# Qwiic_Atmospheric_Sensor.net
KiCad netlist of a schematic drawn in EAGLE
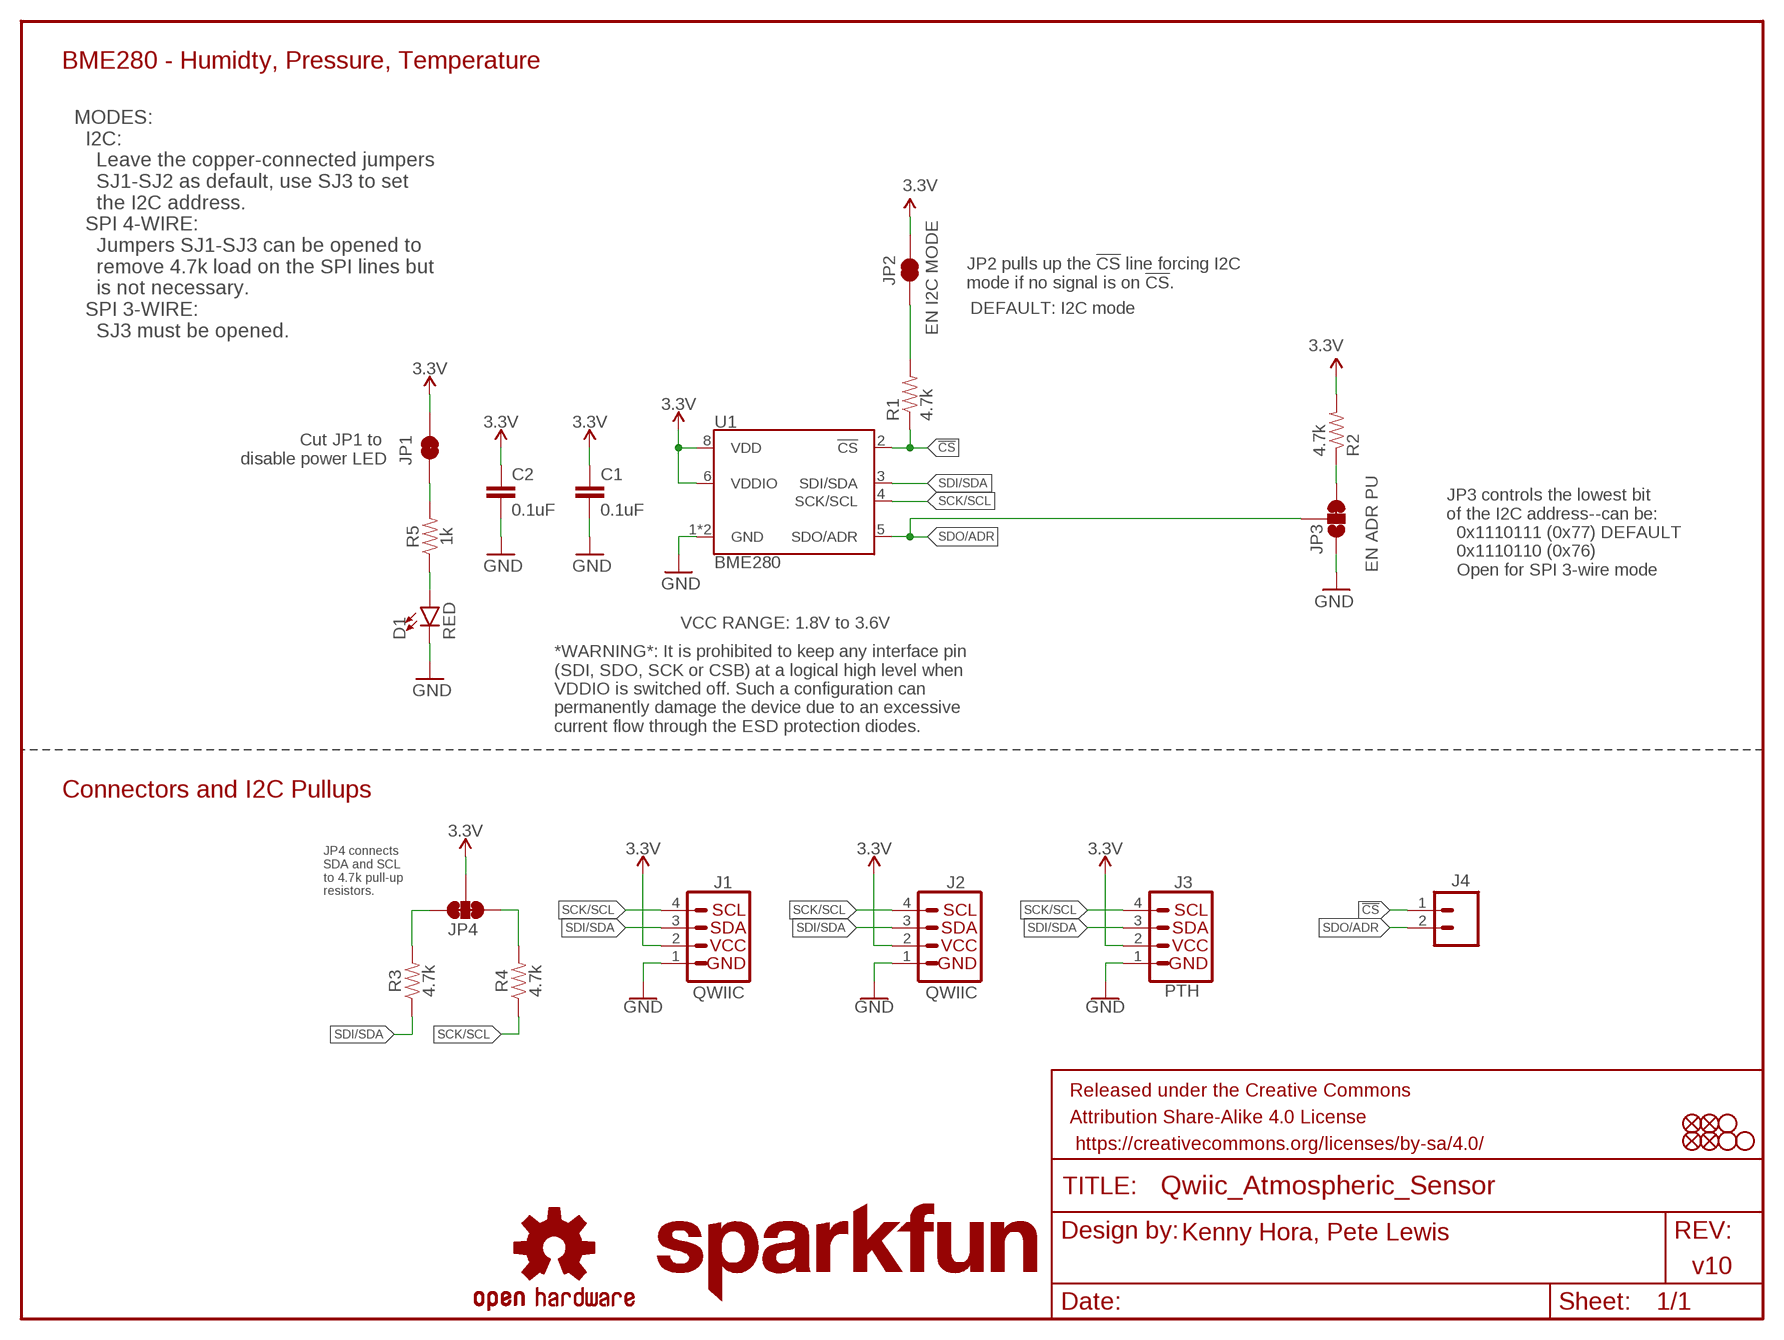
[diagram p0: schematic, sheet 1]

(export (version "E")
  (design (tool "Eeschema 10.0.6"))
  (components
    (comp (ref "C1")
      (value "0.1uF")
      (footprint "eagle-import:0603")
      (libsource (lib "eagle-import") (part "0.1UF-0603-25V-(+80/-20%)"))
    )
    (comp (ref "C2")
      (value "0.1uF")
      (footprint "eagle-import:0603")
      (libsource (lib "eagle-import") (part "0.1UF-0603-25V-(+80/-20%)"))
    )
    (comp (ref "D1")
      (value "RED")
      (footprint "eagle-import:LED-0603")
      (libsource (lib "eagle-import") (part "LED-RED0603"))
    )
    (comp (ref "FD1")
      (value "FIDUCIAL1X2")
      (footprint "eagle-import:FIDUCIAL-1X2")
      (libsource (lib "eagle-import") (part "FIDUCIAL1X2"))
    )
    (comp (ref "FD2")
      (value "FIDUCIAL1X2")
      (footprint "eagle-import:FIDUCIAL-1X2")
      (libsource (lib "eagle-import") (part "FIDUCIAL1X2"))
    )
    (comp (ref "FD3")
      (value "FIDUCIAL1X2")
      (footprint "eagle-import:FIDUCIAL-1X2")
      (libsource (lib "eagle-import") (part "FIDUCIAL1X2"))
    )
    (comp (ref "FD4")
      (value "FIDUCIAL1X2")
      (footprint "eagle-import:FIDUCIAL-1X2")
      (libsource (lib "eagle-import") (part "FIDUCIAL1X2"))
    )
    (comp (ref "FRAME1")
      (value "FRAME-LETTER")
      (footprint "eagle-import:CREATIVE_COMMONS")
      (libsource (lib "eagle-import") (part "FRAME-LETTER"))
    )
    (comp (ref "H1")
      (value "STAND-OFF")
      (footprint "eagle-import:STAND-OFF")
      (libsource (lib "eagle-import") (part "STAND-OFF"))
    )
    (comp (ref "H2")
      (value "STAND-OFF")
      (footprint "eagle-import:STAND-OFF")
      (libsource (lib "eagle-import") (part "STAND-OFF"))
    )
    (comp (ref "H4")
      (value "STAND-OFF")
      (footprint "eagle-import:STAND-OFF")
      (libsource (lib "eagle-import") (part "STAND-OFF"))
    )
    (comp (ref "J1")
      (value "QWIIC")
      (footprint "eagle-import:JST04_1MM_RA")
      (libsource (lib "eagle-import") (part "I2C_STANDARDQWIIC"))
    )
    (comp (ref "J2")
      (value "QWIIC")
      (footprint "eagle-import:JST04_1MM_RA")
      (libsource (lib "eagle-import") (part "I2C_STANDARDQWIIC"))
    )
    (comp (ref "J3")
      (value "PTH")
      (footprint "eagle-import:1X04_NO_SILK")
      (libsource (lib "eagle-import") (part "I2C_STANDARD_NO_SILK"))
    )
    (comp (ref "J4")
      (value "CONN_021X02_NO_SILK")
      (footprint "eagle-import:1X02_NO_SILK")
      (libsource (lib "eagle-import") (part "CONN_021X02_NO_SILK"))
    )
    (comp (ref "JP1")
      (value "JUMPER-SMT_2_NC_TRACE_NO-SILK")
      (footprint "eagle-import:SMT-JUMPER_2_NC_TRACE_NO-SILK")
      (libsource (lib "eagle-import") (part "JUMPER-SMT_2_NC_TRACE_NO-SILK"))
    )
    (comp (ref "JP2")
      (value "EN I2C MODE")
      (footprint "eagle-import:PAD-JUMPER-2-NC_BY_TRACE_NO_SILK")
      (libsource (lib "eagle-import") (part "JUMPER-PAD-2-NC_BY_TRACENO_SILK"))
    )
    (comp (ref "JP3")
      (value "EN ADR PU")
      (footprint "eagle-import:SMT-JUMPER_3_1-NC_TRACE_NO-SILK")
      (libsource (lib "eagle-import") (part "JUMPER-SMT_3_1-NC_TRACE_NO-SILK"))
    )
    (comp (ref "JP4")
      (value "JUMPER-SMT_3_2-NC_TRACE_NO-SILK")
      (footprint "eagle-import:SMT-JUMPER_3_2-NC_TRACE_NO-SILK")
      (libsource (lib "eagle-import") (part "JUMPER-SMT_3_2-NC_TRACE_NO-SILK"))
    )
    (comp (ref "LOGO1")
      (value "SFE_LOGO_NAME.1_INCH")
      (footprint "eagle-import:SFE_LOGO_NAME_.1")
      (libsource (lib "eagle-import") (part "SFE_LOGO_NAME.1_INCH"))
    )
    (comp (ref "LOGO4")
      (value "OSHW-LOGOS")
      (footprint "eagle-import:OSHW-LOGO-S")
      (libsource (lib "eagle-import") (part "OSHW-LOGOS"))
    )
    (comp (ref "R1")
      (value "4.7k")
      (footprint "eagle-import:0603")
      (libsource (lib "eagle-import") (part "4.7KOHM-0603-1/10W-1%"))
    )
    (comp (ref "R2")
      (value "4.7k")
      (footprint "eagle-import:0603")
      (libsource (lib "eagle-import") (part "4.7KOHM-0603-1/10W-1%"))
    )
    (comp (ref "R3")
      (value "4.7k")
      (footprint "eagle-import:0603")
      (libsource (lib "eagle-import") (part "4.7KOHM-0603-1/10W-1%"))
    )
    (comp (ref "R4")
      (value "4.7k")
      (footprint "eagle-import:0603")
      (libsource (lib "eagle-import") (part "4.7KOHM-0603-1/10W-1%"))
    )
    (comp (ref "R5")
      (value "1k")
      (footprint "eagle-import:0603")
      (libsource (lib "eagle-import") (part "1KOHM-0603-1/10W-1%"))
    )
    (comp (ref "U1")
      (value "BME280")
      (footprint "eagle-import:LGA-8-2.5X2.5")
      (libsource (lib "eagle-import") (part "BME280"))
    )
  )
  (nets
    (net (code "1") (name "/~{CS}") (class "Default")
      (node (ref "J4") (pin "1") (pinfunction "1_1") (pintype "passive"))
      (node (ref "R1") (pin "1") (pinfunction "1_1") (pintype "passive"))
      (node (ref "U1") (pin "2") (pinfunction "~{CS}_2") (pintype "bidirectional"))
    )
    (net (code "2") (name "3.3V") (class "Default")
      (node (ref "C1") (pin "1") (pinfunction "1_1") (pintype "passive"))
      (node (ref "C2") (pin "1") (pinfunction "1_1") (pintype "passive"))
      (node (ref "J1") (pin "2") (pinfunction "2_2") (pintype "power_in"))
      (node (ref "J2") (pin "2") (pinfunction "2_2") (pintype "power_in"))
      (node (ref "J3") (pin "2") (pinfunction "2_2") (pintype "power_in"))
      (node (ref "JP1") (pin "2") (pinfunction "2_2") (pintype "passive"))
      (node (ref "JP2") (pin "2") (pinfunction "2_2") (pintype "passive"))
      (node (ref "JP4") (pin "2") (pinfunction "2_2") (pintype "passive"))
      (node (ref "R2") (pin "2") (pinfunction "2_2") (pintype "passive"))
      (node (ref "U1") (pin "6") (pinfunction "VDDIO_6") (pintype "bidirectional"))
      (node (ref "U1") (pin "8") (pinfunction "VDD_8") (pintype "bidirectional"))
    )
    (net (code "3") (name "GND") (class "Default")
      (node (ref "C1") (pin "2") (pinfunction "2_2") (pintype "passive"))
      (node (ref "C2") (pin "2") (pinfunction "2_2") (pintype "passive"))
      (node (ref "D1") (pin "C") (pinfunction "C_C") (pintype "passive"))
      (node (ref "J1") (pin "1") (pinfunction "1_1") (pintype "power_in"))
      (node (ref "J2") (pin "1") (pinfunction "1_1") (pintype "power_in"))
      (node (ref "J3") (pin "1") (pinfunction "1_1") (pintype "power_in"))
      (node (ref "JP3") (pin "1") (pinfunction "1_1") (pintype "passive"))
      (node (ref "U1") (pin "1") (pinfunction "GND_1") (pintype "bidirectional"))
      (node (ref "U1") (pin "7") (pinfunction "GND_7") (pintype "bidirectional"))
    )
    (net (code "4") (name "Net-(D1-PadA)") (class "Default")
      (node (ref "D1") (pin "A") (pinfunction "A_A") (pintype "passive"))
      (node (ref "R5") (pin "1") (pinfunction "1_1") (pintype "passive"))
    )
    (net (code "5") (name "Net-(JP1-Pad1)") (class "Default")
      (node (ref "JP1") (pin "1") (pinfunction "1_1") (pintype "passive"))
      (node (ref "R5") (pin "2") (pinfunction "2_2") (pintype "passive"))
    )
    (net (code "6") (name "Net-(JP2-Pad1)") (class "Default")
      (node (ref "JP2") (pin "1") (pinfunction "1_1") (pintype "passive"))
      (node (ref "R1") (pin "2") (pinfunction "2_2") (pintype "passive"))
    )
    (net (code "7") (name "Net-(JP3-Pad3)") (class "Default")
      (node (ref "JP3") (pin "3") (pinfunction "3_3") (pintype "passive"))
      (node (ref "R2") (pin "1") (pinfunction "1_1") (pintype "passive"))
    )
    (net (code "8") (name "Net-(JP4-Pad1)") (class "Default")
      (node (ref "JP4") (pin "1") (pinfunction "1_1") (pintype "passive"))
      (node (ref "R4") (pin "2") (pinfunction "2_2") (pintype "passive"))
    )
    (net (code "9") (name "Net-(JP4-Pad3)") (class "Default")
      (node (ref "JP4") (pin "3") (pinfunction "3_3") (pintype "passive"))
      (node (ref "R3") (pin "2") (pinfunction "2_2") (pintype "passive"))
    )
    (net (code "10") (name "SCK{slash}SCL") (class "Default")
      (node (ref "J1") (pin "4") (pinfunction "4_4") (pintype "passive"))
      (node (ref "J2") (pin "4") (pinfunction "4_4") (pintype "passive"))
      (node (ref "J3") (pin "4") (pinfunction "4_4") (pintype "passive"))
      (node (ref "R4") (pin "1") (pinfunction "1_1") (pintype "passive"))
      (node (ref "U1") (pin "4") (pinfunction "SCK/SCL_4") (pintype "bidirectional"))
    )
    (net (code "11") (name "SDI{slash}SDA") (class "Default")
      (node (ref "J1") (pin "3") (pinfunction "3_3") (pintype "passive"))
      (node (ref "J2") (pin "3") (pinfunction "3_3") (pintype "passive"))
      (node (ref "J3") (pin "3") (pinfunction "3_3") (pintype "passive"))
      (node (ref "R3") (pin "1") (pinfunction "1_1") (pintype "passive"))
      (node (ref "U1") (pin "3") (pinfunction "SDI/SDA_3") (pintype "bidirectional"))
    )
    (net (code "12") (name "SDO{slash}ADR") (class "Default")
      (node (ref "J4") (pin "2") (pinfunction "2_2") (pintype "passive"))
      (node (ref "JP3") (pin "2") (pinfunction "2_2") (pintype "passive"))
      (node (ref "U1") (pin "5") (pinfunction "SDO/ADR_5") (pintype "bidirectional"))
    )
  )
)
